# hrem.net
KiCad netlist of a schematic drawn in EAGLE
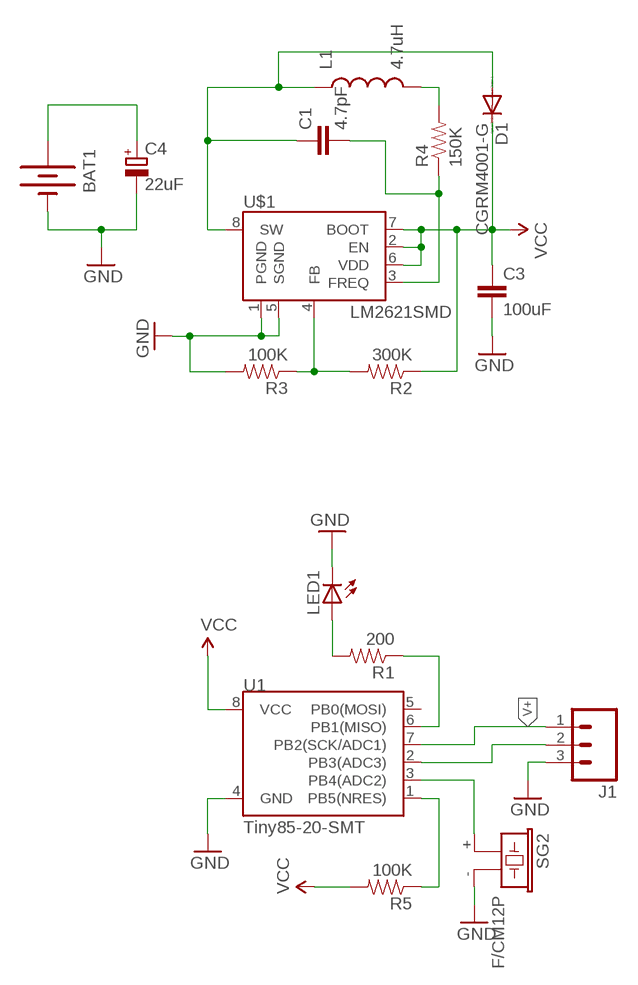
[diagram p0: schematic, sheet 1]

(export (version "E")
  (design (tool "Eeschema 10.0.6"))
  (components
    (comp (ref "BAT1")
      (value "BATTERYAAA")
      (footprint "eagle-import:BATTERY-AAA")
      (libsource (lib "eagle-import") (part "BATTERYAAA"))
    )
    (comp (ref "C1")
      (value "4.7pF")
      (footprint "eagle-import:C1206")
      (libsource (lib "eagle-import") (part "C-EUC1206"))
    )
    (comp (ref "C3")
      (value "100uF")
      (footprint "eagle-import:C1206")
      (libsource (lib "eagle-import") (part "C-EUC1206"))
    )
    (comp (ref "C4")
      (value "22uF")
      (footprint "eagle-import:E2,5-5")
      (libsource (lib "eagle-import") (part "CPOL-EUE2.5-5"))
    )
    (comp (ref "D1")
      (value "CGRM4001-G")
      (footprint "eagle-import:SOD-123_MINI-SMA")
      (libsource (lib "eagle-import") (part "CGRM400-G1"))
    )
    (comp (ref "J1")
      (value "M03PTH")
      (footprint "eagle-import:1X03")
      (libsource (lib "eagle-import") (part "M03PTH"))
    )
    (comp (ref "L1")
      (value "4.7uH")
      (footprint "eagle-import:CR54")
      (libsource (lib "eagle-import") (part "INDUCTORCR54-47UH"))
    )
    (comp (ref "LED1")
      (value "LED3MM")
      (footprint "eagle-import:LED3MM")
      (libsource (lib "eagle-import") (part "LED3MM"))
    )
    (comp (ref "R1")
      (value "200")
      (footprint "eagle-import:1206")
      (libsource (lib "eagle-import") (part "RESISTOR1206"))
    )
    (comp (ref "R2")
      (value "300K")
      (footprint "eagle-import:1206")
      (libsource (lib "eagle-import") (part "RESISTOR1206"))
    )
    (comp (ref "R3")
      (value "100K")
      (footprint "eagle-import:1206")
      (libsource (lib "eagle-import") (part "RESISTOR1206"))
    )
    (comp (ref "R4")
      (value "150K")
      (footprint "eagle-import:1206")
      (libsource (lib "eagle-import") (part "RESISTOR1206"))
    )
    (comp (ref "R5")
      (value "100K")
      (footprint "eagle-import:1206")
      (libsource (lib "eagle-import") (part "RESISTOR1206"))
    )
    (comp (ref "SG2")
      (value "F/CM12P")
      (footprint "eagle-import:F_CM12P")
      (libsource (lib "eagle-import") (part "F/CM12P"))
    )
    (comp (ref "U$1")
      (value "LM2621SMD")
      (footprint "eagle-import:MSOP-8")
      (libsource (lib "eagle-import") (part "LM2621SMD"))
    )
    (comp (ref "U1")
      (value "Tiny85-20-SMT")
      (footprint "eagle-import:SO08-EIAJ")
      (libsource (lib "eagle-import") (part "ATTINY45TINY85-20-SMT"))
    )
  )
  (nets
    (net (code "1") (name "GND") (class "Default")
      (node (ref "BAT1") (pin "GND@1") (pinfunction "-_GND@1") (pintype "power_in"))
      (node (ref "C3") (pin "2") (pinfunction "2_2") (pintype "passive"))
      (node (ref "C4") (pin "-") (pinfunction "-_-") (pintype "passive"))
      (node (ref "J1") (pin "3") (pinfunction "3_3") (pintype "passive"))
      (node (ref "LED1") (pin "K") (pinfunction "C_K") (pintype "passive"))
      (node (ref "R3") (pin "2") (pinfunction "2_2") (pintype "passive"))
      (node (ref "SG2") (pin "-") (pinfunction "2_-") (pintype "passive"))
      (node (ref "U$1") (pin "1") (pinfunction "PGND_1") (pintype "bidirectional"))
      (node (ref "U$1") (pin "5") (pinfunction "SGND_5") (pintype "bidirectional"))
      (node (ref "U1") (pin "4") (pinfunction "GND_4") (pintype "bidirectional"))
    )
    (net (code "2") (name "Net-(BAT1-+)") (class "Default")
      (node (ref "BAT1") (pin "PWR@1") (pinfunction "+_PWR@1") (pintype "power_in"))
      (node (ref "C4") (pin "+") (pinfunction "+_+") (pintype "passive"))
    )
    (net (code "3") (name "Net-(L1-1)") (class "Default")
      (node (ref "C1") (pin "1") (pinfunction "1_1") (pintype "passive"))
      (node (ref "D1") (pin "A") (pinfunction "A_A") (pintype "passive"))
      (node (ref "L1") (pin "P$1") (pinfunction "1_P$1") (pintype "passive"))
      (node (ref "U$1") (pin "8") (pinfunction "SW_8") (pintype "bidirectional"))
    )
    (net (code "4") (name "Net-(L1-2)") (class "Default")
      (node (ref "L1") (pin "P$2") (pinfunction "2_P$2") (pintype "passive"))
      (node (ref "R4") (pin "2") (pinfunction "2_2") (pintype "passive"))
    )
    (net (code "5") (name "Net-(LED1-PadA)") (class "Default")
      (node (ref "LED1") (pin "A") (pinfunction "A_A") (pintype "passive"))
      (node (ref "R1") (pin "2") (pinfunction "2_2") (pintype "passive"))
    )
    (net (code "6") (name "Net-(SG2-1)") (class "Default")
      (node (ref "SG2") (pin "+") (pinfunction "1_+") (pintype "passive"))
      (node (ref "U1") (pin "3") (pinfunction "PB4(ADC2)_3") (pintype "bidirectional"))
    )
    (net (code "7") (name "Net-(U$1-FB)") (class "Default")
      (node (ref "R2") (pin "2") (pinfunction "2_2") (pintype "passive"))
      (node (ref "R3") (pin "1") (pinfunction "1_1") (pintype "passive"))
      (node (ref "U$1") (pin "4") (pinfunction "FB_4") (pintype "bidirectional"))
    )
    (net (code "8") (name "Net-(U$1-FREQ)") (class "Default")
      (node (ref "C1") (pin "2") (pinfunction "2_2") (pintype "passive"))
      (node (ref "R4") (pin "1") (pinfunction "1_1") (pintype "passive"))
      (node (ref "U$1") (pin "3") (pinfunction "FREQ_3") (pintype "bidirectional"))
    )
    (net (code "9") (name "Net-(U1-PB1(MISO))") (class "Default")
      (node (ref "R1") (pin "1") (pinfunction "1_1") (pintype "passive"))
      (node (ref "U1") (pin "6") (pinfunction "PB1(MISO)_6") (pintype "bidirectional"))
    )
    (net (code "10") (name "Net-(U1-PB3(ADC3))") (class "Default")
      (node (ref "J1") (pin "2") (pinfunction "2_2") (pintype "passive"))
      (node (ref "U1") (pin "2") (pinfunction "PB3(ADC3)_2") (pintype "bidirectional"))
    )
    (net (code "11") (name "Net-(U1-PB5(NRES))") (class "Default")
      (node (ref "R5") (pin "1") (pinfunction "1_1") (pintype "passive"))
      (node (ref "U1") (pin "1") (pinfunction "PB5(NRES)_1") (pintype "bidirectional"))
    )
    (net (code "12") (name "V+") (class "Default")
      (node (ref "J1") (pin "1") (pinfunction "1_1") (pintype "passive"))
      (node (ref "U1") (pin "7") (pinfunction "PB2(SCK/ADC1)_7") (pintype "bidirectional"))
    )
    (net (code "13") (name "VCC") (class "Default")
      (node (ref "C3") (pin "1") (pinfunction "1_1") (pintype "passive"))
      (node (ref "D1") (pin "C") (pinfunction "C_C") (pintype "passive"))
      (node (ref "R2") (pin "1") (pinfunction "1_1") (pintype "passive"))
      (node (ref "R5") (pin "2") (pinfunction "2_2") (pintype "passive"))
      (node (ref "U$1") (pin "2") (pinfunction "EN_2") (pintype "bidirectional"))
      (node (ref "U$1") (pin "6") (pinfunction "VDD_6") (pintype "bidirectional"))
      (node (ref "U$1") (pin "7") (pinfunction "BOOT_7") (pintype "bidirectional"))
      (node (ref "U1") (pin "8") (pinfunction "VCC_8") (pintype "bidirectional"))
    )
    (net (code "14") (name "unconnected-(U1-PB0(MOSI)-Pad5)") (class "Default")
      (node (ref "U1") (pin "5") (pinfunction "PB0(MOSI)_5") (pintype "bidirectional"))
    )
  )
)
